# nixi_board_zm_1080.net
KiCad netlist of a schematic drawn in EAGLE
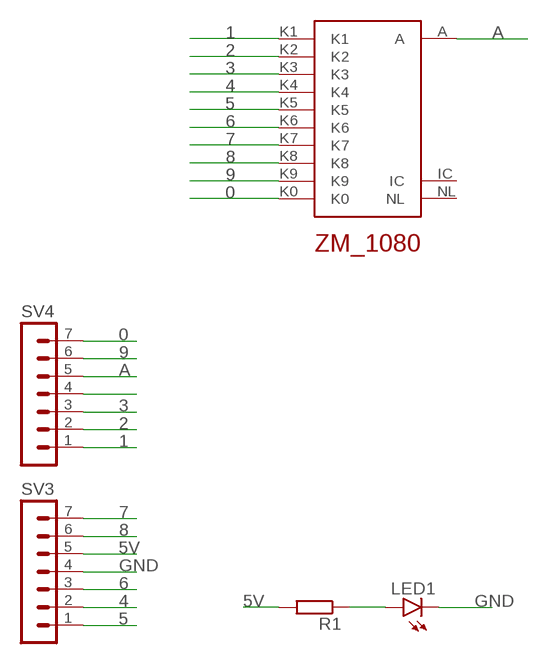
[diagram p0: schematic, sheet 1]

(export (version "E")
  (design (tool "Eeschema 10.0.6"))
  (components
    (comp (ref "LED1")
      (value "LEDSMT1206")
      (footprint "eagle-import:1206")
      (libsource (lib "eagle-import") (part "LEDSMT1206"))
    )
    (comp (ref "R1")
      (value "R-EU_R1206")
      (footprint "eagle-import:R1206")
      (libsource (lib "eagle-import") (part "R-EU_R1206"))
    )
    (comp (ref "SV3")
      (value "MA07-1")
      (footprint "eagle-import:MA07-1")
      (libsource (lib "eagle-import") (part "MA07-1"))
    )
    (comp (ref "SV4")
      (value "MA07-1")
      (footprint "eagle-import:MA07-1")
      (libsource (lib "eagle-import") (part "MA07-1"))
    )
    (comp (ref "U$2")
      (value "ZM_1080")
      (footprint "eagle-import:ZM_1080")
      (libsource (lib "eagle-import") (part "ZM_1080"))
    )
  )
  (nets
    (net (code "1") (name "/0") (class "Default")
      (node (ref "SV4") (pin "7") (pinfunction "7_7") (pintype "passive"))
      (node (ref "U$2") (pin "K0") (pinfunction "K0_K0") (pintype "bidirectional"))
    )
    (net (code "2") (name "/1") (class "Default")
      (node (ref "SV4") (pin "1") (pinfunction "1_1") (pintype "passive"))
      (node (ref "U$2") (pin "K1") (pinfunction "K1_K1") (pintype "bidirectional"))
    )
    (net (code "3") (name "/2") (class "Default")
      (node (ref "SV4") (pin "2") (pinfunction "2_2") (pintype "passive"))
      (node (ref "U$2") (pin "K2") (pinfunction "K2_K2") (pintype "bidirectional"))
    )
    (net (code "4") (name "/3") (class "Default")
      (node (ref "SV4") (pin "3") (pinfunction "3_3") (pintype "passive"))
      (node (ref "U$2") (pin "K3") (pinfunction "K3_K3") (pintype "bidirectional"))
    )
    (net (code "5") (name "/4") (class "Default")
      (node (ref "SV3") (pin "2") (pinfunction "2_2") (pintype "passive"))
      (node (ref "U$2") (pin "K4") (pinfunction "K4_K4") (pintype "bidirectional"))
    )
    (net (code "6") (name "/5") (class "Default")
      (node (ref "SV3") (pin "1") (pinfunction "1_1") (pintype "passive"))
      (node (ref "U$2") (pin "K5") (pinfunction "K5_K5") (pintype "bidirectional"))
    )
    (net (code "7") (name "/5V") (class "Default")
      (node (ref "R1") (pin "2") (pinfunction "2_2") (pintype "passive"))
      (node (ref "SV3") (pin "5") (pinfunction "5_5") (pintype "passive"))
    )
    (net (code "8") (name "/6") (class "Default")
      (node (ref "SV3") (pin "3") (pinfunction "3_3") (pintype "passive"))
      (node (ref "U$2") (pin "K6") (pinfunction "K6_K6") (pintype "bidirectional"))
    )
    (net (code "9") (name "/7") (class "Default")
      (node (ref "SV3") (pin "7") (pinfunction "7_7") (pintype "passive"))
      (node (ref "U$2") (pin "K7") (pinfunction "K7_K7") (pintype "bidirectional"))
    )
    (net (code "10") (name "/8") (class "Default")
      (node (ref "SV3") (pin "6") (pinfunction "6_6") (pintype "passive"))
      (node (ref "U$2") (pin "K8") (pinfunction "K8_K8") (pintype "bidirectional"))
    )
    (net (code "11") (name "/9") (class "Default")
      (node (ref "SV4") (pin "6") (pinfunction "6_6") (pintype "passive"))
      (node (ref "U$2") (pin "K9") (pinfunction "K9_K9") (pintype "bidirectional"))
    )
    (net (code "12") (name "/A") (class "Default")
      (node (ref "SV4") (pin "5") (pinfunction "5_5") (pintype "passive"))
      (node (ref "U$2") (pin "A") (pinfunction "A_A") (pintype "bidirectional"))
    )
    (net (code "13") (name "/GND") (class "Default")
      (node (ref "LED1") (pin "C") (pinfunction "C_C") (pintype "passive"))
      (node (ref "SV3") (pin "4") (pinfunction "4_4") (pintype "passive"))
    )
    (net (code "14") (name "Net-(LED1-PadA)") (class "Default")
      (node (ref "LED1") (pin "A") (pinfunction "A_A") (pintype "passive"))
      (node (ref "R1") (pin "1") (pinfunction "1_1") (pintype "passive"))
    )
    (net (code "15") (name "unconnected-(SV4-Pad4)") (class "Default")
      (node (ref "SV4") (pin "4") (pinfunction "4_4") (pintype "passive"))
    )
    (net (code "16") (name "unconnected-(U$2-PadIC)") (class "Default")
      (node (ref "U$2") (pin "IC") (pinfunction "IC_IC") (pintype "bidirectional"))
    )
    (net (code "17") (name "unconnected-(U$2-PadNL)") (class "Default")
      (node (ref "U$2") (pin "NL") (pinfunction "NL_NL") (pintype "bidirectional"))
    )
  )
)
